# LTC.net
KiCad netlist of a schematic drawn in Altium Designer
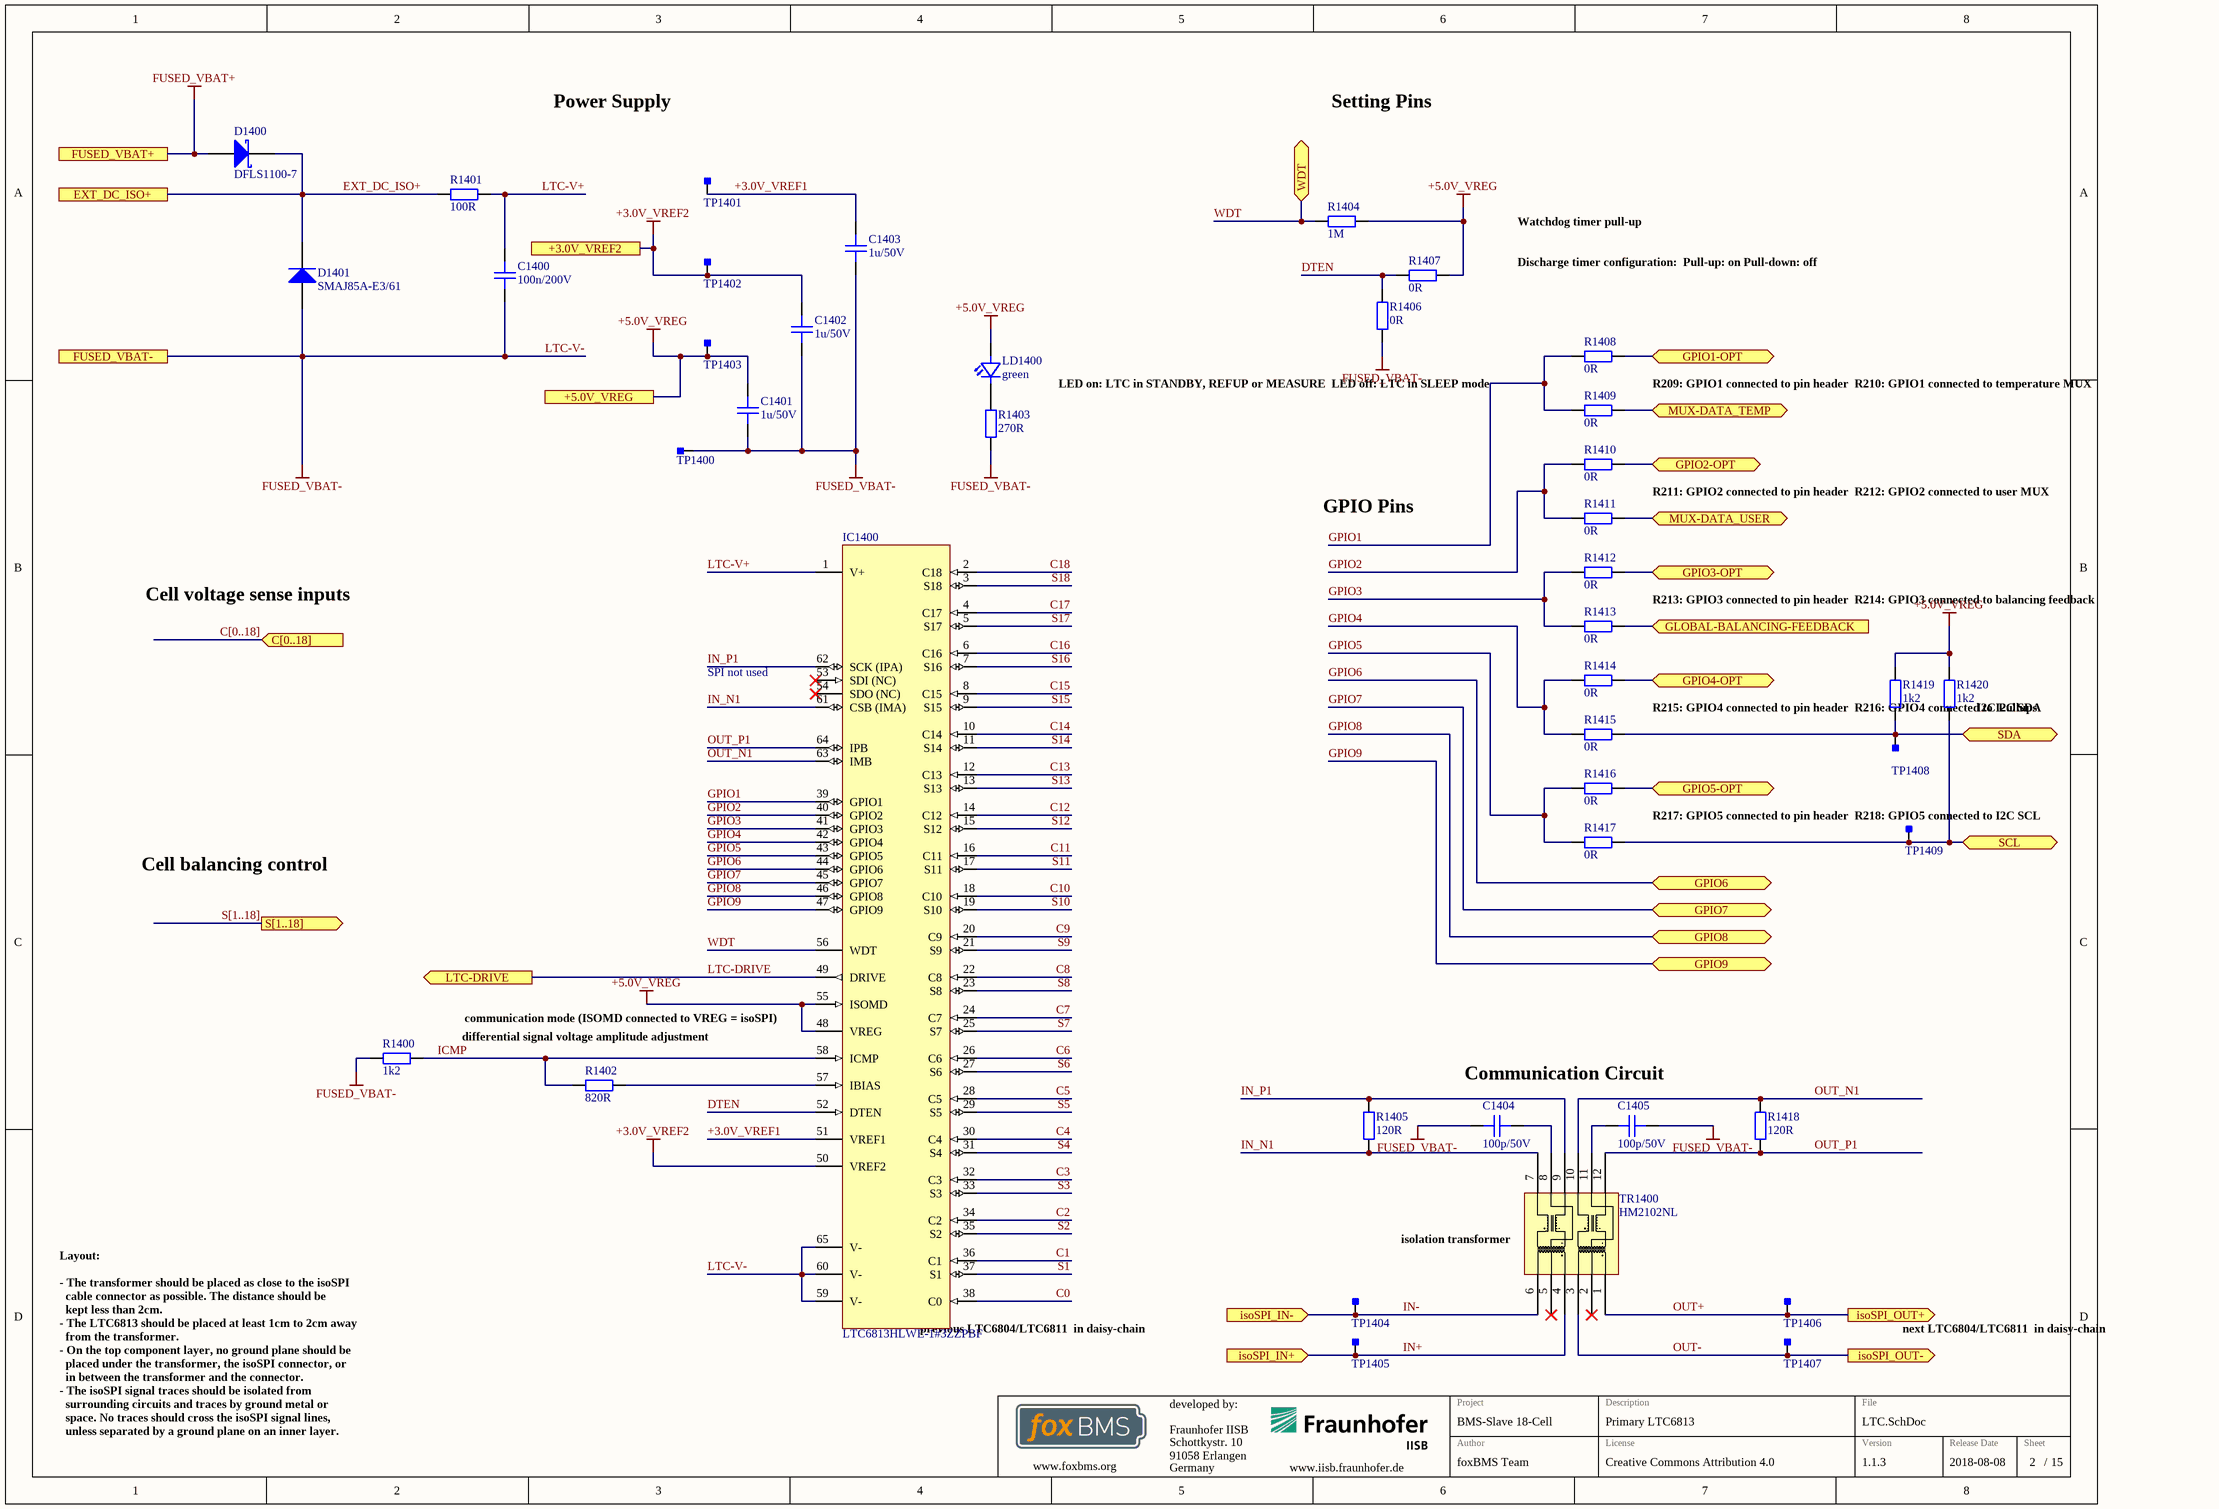
[diagram p0: LTC.SchDoc]

(export (version "E")
  (design (tool "Eeschema 10.0.6"))
  (components
    (comp (ref "C1400")
      (value "100n/200V")
      (footprint "CAPC3216X18N")
      (description "MLCC")
      (fields (field (name "PART NUMBER") "gen_C_ceramic_100n_200V_X7R_1206"))
      (libsource (lib "OE750") (part "C"))
    )
    (comp (ref "C1401")
      (value "1u/50V")
      (footprint "CAPC2012X14N")
      (description "MLCC")
      (fields (field (name "PART NUMBER") "gen_C_ceramic_1u_50V_X7R_0805") (field (name "TOLERANCE") "± 10%"))
      (libsource (lib "OE750") (part "C"))
    )
    (comp (ref "C1402")
      (value "1u/50V")
      (footprint "CAPC2012X14N")
      (description "MLCC")
      (fields (field (name "PART NUMBER") "gen_C_ceramic_1u_50V_X7R_0805") (field (name "TOLERANCE") "± 10%"))
      (libsource (lib "OE750") (part "C"))
    )
    (comp (ref "C1403")
      (value "1u/50V")
      (footprint "CAPC2012X14N")
      (description "MLCC")
      (fields (field (name "PART NUMBER") "gen_C_ceramic_1u_50V_X7R_0805") (field (name "TOLERANCE") "± 10%"))
      (libsource (lib "OE750") (part "C"))
    )
    (comp (ref "C1404")
      (value "100p/50V")
      (footprint "CAPC1608X08N")
      (description "MLCC")
      (fields
        (field (name "PART NUMBER") "gen_C_ceramic_100p_50V_C0G_0603")
        (field (name "TOLERANCE") "± 10%")
      )
      (libsource (lib "OE750") (part "C"))
    )
    (comp (ref "C1405")
      (value "100p/50V")
      (footprint "CAPC1608X08N")
      (description "MLCC")
      (fields
        (field (name "PART NUMBER") "gen_C_ceramic_100p_50V_C0G_0603")
        (field (name "TOLERANCE") "± 10%")
      )
      (libsource (lib "OE750") (part "C"))
    )
    (comp (ref "D1400")
      (value "DFLS1100-7")
      (footprint "DIOD-POWERDI123-2_V")
      (fields (field (name "MANUFACTURER") "Diodes Inc"))
      (libsource (lib "Altium Content Vault") (part "DSKY-AK-2"))
    )
    (comp (ref "D1401")
      (value "SMAJ85A-E3/61")
      (footprint "VISH-DO-214AC-2_L")
      (fields (field (name "MANUFACTURER") "Vishay Semiconductor"))
      (libsource (lib "Altium Content Vault") (part "VISH-K1A2-2"))
    )
    (comp (ref "IC1400")
      (value "LTC6813HLWE-1#3ZZPBF")
      (footprint "TSQFP50P1200X1200X160_HS-65N")
      (description "18 Cell Multicell Battery Monitor, -40 to 125 degC, Pb-Free")
      (fields (field (name "PARTNUMBER") "LTC6811HG-1#PBF") (field (name "MANUFACTURER") "Linear Technology"))
      (libsource (lib "OE750") (part "LTC6813HLWE-1#3ZZPBF"))
    )
    (comp (ref "LD1400")
      (value "green")
      (footprint "LEDC1608X07N")
      (description "TLMG1100-GS08")
      (fields (field (name "PART NUMBER") "LED_0603_green_AECQ") (field (name "MANUFACTURER") "Vishay"))
      (libsource (lib "OE750") (part "D_LED"))
    )
    (comp (ref "R1400")
      (value "1k2")
      (footprint "RESC1608X05N")
      (description "SMD Resistor 1k2 0603")
      (fields (field (name "PART NUMBER") "gen_R_1k2_0603") (field (name "TOLERANCE") "1%"))
      (libsource (lib "OE750") (part "R"))
    )
    (comp (ref "R1401")
      (value "100R")
      (footprint "RESC2012X05N")
      (description "SMD Resistor 100R 0805")
      (fields (field (name "PART NUMBER") "gen_R_100R_0805") (field (name "TOLERANCE") "1%"))
      (libsource (lib "OE750") (part "R"))
    )
    (comp (ref "R1402")
      (value "820R")
      (footprint "RESC1608X05N")
      (description "SMD Resistor 820R 0603")
      (fields (field (name "PART NUMBER") "gen_R_820R_0603") (field (name "TOLERANCE") "1%"))
      (libsource (lib "OE750") (part "R"))
    )
    (comp (ref "R1403")
      (value "270R")
      (footprint "RESC1608X05N")
      (description "SMD Resistor 270R 0603")
      (fields (field (name "PART NUMBER") "gen_R_270R_0603") (field (name "TOLERANCE") "1%"))
      (libsource (lib "OE750") (part "R"))
    )
    (comp (ref "R1404")
      (value "1M")
      (footprint "RESC1608X05N")
      (description "SMD Resistor 1M 0603")
      (fields (field (name "PART NUMBER") "gen_R_1M_0603") (field (name "TOLERANCE") "1%"))
      (libsource (lib "OE750") (part "R"))
    )
    (comp (ref "R1405")
      (value "120R")
      (footprint "RESC1608X05N")
      (description "SMD Resistor 120R 0603")
      (fields (field (name "PART NUMBER") "gen_R_120R_0603") (field (name "TOLERANCE") "1%"))
      (libsource (lib "OE750") (part "R"))
    )
    (comp (ref "R1406")
      (value "0R")
      (footprint "RESC1608X05N")
      (description "SMD Resistor 0R 0603")
      (fields (field (name "PART NUMBER") "gen_R_0R_0603") (field (name "POWER") "0.1W"))
      (libsource (lib "OE750") (part "R"))
    )
    (comp (ref "R1407")
      (value "0R")
      (footprint "RESC1608X05N")
      (description "SMD Resistor 0R 0603")
      (fields (field (name "PART NUMBER") "gen_R_0R_0603") (field (name "POWER") "0.1W"))
      (libsource (lib "OE750") (part "R"))
    )
    (comp (ref "R1408")
      (value "0R")
      (footprint "RESC1608X05N")
      (description "SMD Resistor 0R 0603")
      (fields (field (name "PART NUMBER") "gen_R_0R_0603") (field (name "POWER") "0.1W"))
      (libsource (lib "OE750") (part "R"))
    )
    (comp (ref "R1409")
      (value "0R")
      (footprint "RESC1608X05N")
      (description "SMD Resistor 0R 0603")
      (fields (field (name "PART NUMBER") "gen_R_0R_0603") (field (name "POWER") "0.1W"))
      (libsource (lib "OE750") (part "R"))
    )
    (comp (ref "R1410")
      (value "0R")
      (footprint "RESC1608X05N")
      (description "SMD Resistor 0R 0603")
      (fields (field (name "PART NUMBER") "gen_R_0R_0603") (field (name "POWER") "0.1W"))
      (libsource (lib "OE750") (part "R"))
    )
    (comp (ref "R1411")
      (value "0R")
      (footprint "RESC1608X05N")
      (description "SMD Resistor 0R 0603")
      (fields (field (name "PART NUMBER") "gen_R_0R_0603") (field (name "POWER") "0.1W"))
      (libsource (lib "OE750") (part "R"))
    )
    (comp (ref "R1412")
      (value "0R")
      (footprint "RESC1608X05N")
      (description "SMD Resistor 0R 0603")
      (fields (field (name "PART NUMBER") "gen_R_0R_0603") (field (name "POWER") "0.1W"))
      (libsource (lib "OE750") (part "R"))
    )
    (comp (ref "R1413")
      (value "0R")
      (footprint "RESC1608X05N")
      (description "SMD Resistor 0R 0603")
      (fields (field (name "PART NUMBER") "gen_R_0R_0603") (field (name "POWER") "0.1W"))
      (libsource (lib "OE750") (part "R"))
    )
    (comp (ref "R1414")
      (value "0R")
      (footprint "RESC1608X05N")
      (description "SMD Resistor 0R 0603")
      (fields (field (name "PART NUMBER") "gen_R_0R_0603") (field (name "POWER") "0.1W"))
      (libsource (lib "OE750") (part "R"))
    )
    (comp (ref "R1415")
      (value "0R")
      (footprint "RESC1608X05N")
      (description "SMD Resistor 0R 0603")
      (fields (field (name "PART NUMBER") "gen_R_0R_0603") (field (name "POWER") "0.1W"))
      (libsource (lib "OE750") (part "R"))
    )
    (comp (ref "R1416")
      (value "0R")
      (footprint "RESC1608X05N")
      (description "SMD Resistor 0R 0603")
      (fields (field (name "PART NUMBER") "gen_R_0R_0603") (field (name "POWER") "0.1W"))
      (libsource (lib "OE750") (part "R"))
    )
    (comp (ref "R1417")
      (value "0R")
      (footprint "RESC1608X05N")
      (description "SMD Resistor 0R 0603")
      (fields (field (name "PART NUMBER") "gen_R_0R_0603") (field (name "POWER") "0.1W"))
      (libsource (lib "OE750") (part "R"))
    )
    (comp (ref "R1418")
      (value "120R")
      (footprint "RESC1608X05N")
      (description "SMD Resistor 120R 0603")
      (fields (field (name "PART NUMBER") "gen_R_120R_0603") (field (name "TOLERANCE") "1%"))
      (libsource (lib "OE750") (part "R"))
    )
    (comp (ref "R1419")
      (value "1k2")
      (footprint "RESC1608X05N")
      (description "SMD Resistor 1k2 0603")
      (fields (field (name "PART NUMBER") "gen_R_1k2_0603") (field (name "TOLERANCE") "1%"))
      (libsource (lib "OE750") (part "R"))
    )
    (comp (ref "R1420")
      (value "1k2")
      (footprint "RESC1608X05N")
      (description "SMD Resistor 1k2 0603")
      (fields (field (name "PART NUMBER") "gen_R_1k2_0603") (field (name "TOLERANCE") "1%"))
      (libsource (lib "OE750") (part "R"))
    )
    (comp (ref "TP1400")
      (value "Testpoint_Square")
      (footprint "Testpoint_S1")
      (description "Testpoint, square")
      (libsource (lib "OE750") (part "Testpoint_Square"))
    )
    (comp (ref "TP1401")
      (value "Testpoint_Square")
      (footprint "Testpoint_S1")
      (description "Testpoint, square")
      (libsource (lib "OE750") (part "Testpoint_Square"))
    )
    (comp (ref "TP1402")
      (value "Testpoint_Square")
      (footprint "Testpoint_S1")
      (description "Testpoint, square")
      (libsource (lib "OE750") (part "Testpoint_Square"))
    )
    (comp (ref "TP1403")
      (value "Testpoint_Square")
      (footprint "Testpoint_S1")
      (description "Testpoint, square")
      (libsource (lib "OE750") (part "Testpoint_Square"))
    )
    (comp (ref "TP1404")
      (value "Testpoint_Square")
      (footprint "Testpoint_S1")
      (description "Testpoint, square")
      (libsource (lib "OE750") (part "Testpoint_Square"))
    )
    (comp (ref "TP1405")
      (value "Testpoint_Square")
      (footprint "Testpoint_S1")
      (description "Testpoint, square")
      (libsource (lib "OE750") (part "Testpoint_Square"))
    )
    (comp (ref "TP1406")
      (value "Testpoint_Square")
      (footprint "Testpoint_S1")
      (description "Testpoint, square")
      (libsource (lib "OE750") (part "Testpoint_Square"))
    )
    (comp (ref "TP1407")
      (value "Testpoint_Square")
      (footprint "Testpoint_S1")
      (description "Testpoint, square")
      (libsource (lib "OE750") (part "Testpoint_Square"))
    )
    (comp (ref "TP1408")
      (value "Testpoint_Square")
      (footprint "Testpoint_S1")
      (description "Testpoint, square")
      (libsource (lib "OE750") (part "Testpoint_Square"))
    )
    (comp (ref "TP1409")
      (value "Testpoint_Square")
      (footprint "Testpoint_S1")
      (description "Testpoint, square")
      (libsource (lib "OE750") (part "Testpoint_Square"))
    )
    (comp (ref "TR1400")
      (value "HM2102NL")
      (footprint "HM2102NL")
      (description "Pulse HM2102NL BMS Transformer")
      (fields (field (name "MANUFACTURER") "Pulse"))
      (libsource (lib "OE750") (part "HM2102NL"))
    )
  )
  (nets
    (net (code "1") (name "+3.0V_VREF2") (class "Default")
      (node (ref "C1402") (pin "2") (pinfunction "2_2") (pintype "passive"))
      (node (ref "IC1400") (pin "50") (pinfunction "VREF2_50") (pintype "passive"))
      (node (ref "TP1402") (pin "1") (pinfunction "1_1") (pintype "passive"))
    )
    (net (code "2") (name "+5.0V_VREG") (class "Default")
      (node (ref "C1401") (pin "2") (pinfunction "2_2") (pintype "passive"))
      (node (ref "IC1400") (pin "48") (pinfunction "VREG_48") (pintype "power_in"))
      (node (ref "IC1400") (pin "55") (pinfunction "ISOMD_55") (pintype "input"))
      (node (ref "LD1400") (pin "2") (pinfunction "A_2") (pintype "passive"))
      (node (ref "R1404") (pin "2") (pinfunction "2_2") (pintype "passive"))
      (node (ref "R1407") (pin "2") (pinfunction "2_2") (pintype "passive"))
      (node (ref "R1419") (pin "2") (pinfunction "2_2") (pintype "passive"))
      (node (ref "R1420") (pin "2") (pinfunction "2_2") (pintype "passive"))
      (node (ref "TP1403") (pin "1") (pinfunction "1_1") (pintype "passive"))
    )
    (net (code "3") (name "/+3.0V_VREF1") (class "Default")
      (node (ref "C1403") (pin "2") (pinfunction "2_2") (pintype "passive"))
      (node (ref "IC1400") (pin "51") (pinfunction "VREF1_51") (pintype "passive"))
      (node (ref "TP1401") (pin "1") (pinfunction "1_1") (pintype "passive"))
    )
    (net (code "4") (name "/C0") (class "Default")
      (node (ref "IC1400") (pin "38") (pinfunction "C0_38") (pintype "input"))
    )
    (net (code "5") (name "/C1") (class "Default")
      (node (ref "IC1400") (pin "36") (pinfunction "C1_36") (pintype "input"))
    )
    (net (code "6") (name "/C2") (class "Default")
      (node (ref "IC1400") (pin "34") (pinfunction "C2_34") (pintype "input"))
    )
    (net (code "7") (name "/C3") (class "Default")
      (node (ref "IC1400") (pin "32") (pinfunction "C3_32") (pintype "input"))
    )
    (net (code "8") (name "/C4") (class "Default")
      (node (ref "IC1400") (pin "30") (pinfunction "C4_30") (pintype "input"))
    )
    (net (code "9") (name "/C5") (class "Default")
      (node (ref "IC1400") (pin "28") (pinfunction "C5_28") (pintype "input"))
    )
    (net (code "10") (name "/C6") (class "Default")
      (node (ref "IC1400") (pin "26") (pinfunction "C6_26") (pintype "input"))
    )
    (net (code "11") (name "/C7") (class "Default")
      (node (ref "IC1400") (pin "24") (pinfunction "C7_24") (pintype "input"))
    )
    (net (code "12") (name "/C8") (class "Default")
      (node (ref "IC1400") (pin "22") (pinfunction "C8_22") (pintype "input"))
    )
    (net (code "13") (name "/C9") (class "Default")
      (node (ref "IC1400") (pin "20") (pinfunction "C9_20") (pintype "input"))
    )
    (net (code "14") (name "/C10") (class "Default")
      (node (ref "IC1400") (pin "18") (pinfunction "C10_18") (pintype "input"))
    )
    (net (code "15") (name "/C11") (class "Default")
      (node (ref "IC1400") (pin "16") (pinfunction "C11_16") (pintype "input"))
    )
    (net (code "16") (name "/C12") (class "Default")
      (node (ref "IC1400") (pin "14") (pinfunction "C12_14") (pintype "input"))
    )
    (net (code "17") (name "/C13") (class "Default")
      (node (ref "IC1400") (pin "12") (pinfunction "C13_12") (pintype "input"))
    )
    (net (code "18") (name "/C14") (class "Default")
      (node (ref "IC1400") (pin "10") (pinfunction "C14_10") (pintype "input"))
    )
    (net (code "19") (name "/C15") (class "Default")
      (node (ref "IC1400") (pin "8") (pinfunction "C15_8") (pintype "input"))
    )
    (net (code "20") (name "/C16") (class "Default")
      (node (ref "IC1400") (pin "6") (pinfunction "C16_6") (pintype "input"))
    )
    (net (code "21") (name "/C17") (class "Default")
      (node (ref "IC1400") (pin "4") (pinfunction "C17_4") (pintype "input"))
    )
    (net (code "22") (name "/C18") (class "Default")
      (node (ref "IC1400") (pin "2") (pinfunction "C18_2") (pintype "input"))
    )
    (net (code "24") (name "/DTEN") (class "Default")
      (node (ref "IC1400") (pin "52") (pinfunction "DTEN_52") (pintype "input"))
      (node (ref "R1406") (pin "2") (pinfunction "2_2") (pintype "passive"))
      (node (ref "R1407") (pin "1") (pinfunction "1_1") (pintype "passive"))
    )
    (net (code "25") (name "/EXT_DC_ISO+") (class "Default")
      (node (ref "D1400") (pin "2") (pinfunction "K_2") (pintype "passive"))
      (node (ref "D1401") (pin "1") (pinfunction "K_1") (pintype "passive"))
      (node (ref "R1401") (pin "1") (pinfunction "1_1") (pintype "passive"))
    )
    (net (code "26") (name "/GLOBAL-BALANCING-FEEDBACK") (class "Default")
      (node (ref "R1413") (pin "1") (pinfunction "1_1") (pintype "passive"))
    )
    (net (code "27") (name "/GPIO1") (class "Default")
      (node (ref "IC1400") (pin "39") (pinfunction "GPIO1_39") (pintype "bidirectional"))
      (node (ref "R1408") (pin "2") (pinfunction "2_2") (pintype "passive"))
      (node (ref "R1409") (pin "2") (pinfunction "2_2") (pintype "passive"))
    )
    (net (code "28") (name "/GPIO1-OPT") (class "Default")
      (node (ref "R1408") (pin "1") (pinfunction "1_1") (pintype "passive"))
    )
    (net (code "29") (name "/GPIO2") (class "Default")
      (node (ref "IC1400") (pin "40") (pinfunction "GPIO2_40") (pintype "bidirectional"))
      (node (ref "R1410") (pin "2") (pinfunction "2_2") (pintype "passive"))
      (node (ref "R1411") (pin "2") (pinfunction "2_2") (pintype "passive"))
    )
    (net (code "30") (name "/GPIO2-OPT") (class "Default")
      (node (ref "R1410") (pin "1") (pinfunction "1_1") (pintype "passive"))
    )
    (net (code "31") (name "/GPIO3") (class "Default")
      (node (ref "IC1400") (pin "41") (pinfunction "GPIO3_41") (pintype "bidirectional"))
      (node (ref "R1412") (pin "2") (pinfunction "2_2") (pintype "passive"))
      (node (ref "R1413") (pin "2") (pinfunction "2_2") (pintype "passive"))
    )
    (net (code "32") (name "/GPIO3-OPT") (class "Default")
      (node (ref "R1412") (pin "1") (pinfunction "1_1") (pintype "passive"))
    )
    (net (code "33") (name "/GPIO4") (class "Default")
      (node (ref "IC1400") (pin "42") (pinfunction "GPIO4_42") (pintype "bidirectional"))
      (node (ref "R1414") (pin "2") (pinfunction "2_2") (pintype "passive"))
      (node (ref "R1415") (pin "2") (pinfunction "2_2") (pintype "passive"))
    )
    (net (code "34") (name "/GPIO4-OPT") (class "Default")
      (node (ref "R1414") (pin "1") (pinfunction "1_1") (pintype "passive"))
    )
    (net (code "35") (name "/GPIO5") (class "Default")
      (node (ref "IC1400") (pin "43") (pinfunction "GPIO5_43") (pintype "bidirectional"))
      (node (ref "R1416") (pin "2") (pinfunction "2_2") (pintype "passive"))
      (node (ref "R1417") (pin "2") (pinfunction "2_2") (pintype "passive"))
    )
    (net (code "36") (name "/GPIO5-OPT") (class "Default")
      (node (ref "R1416") (pin "1") (pinfunction "1_1") (pintype "passive"))
    )
    (net (code "37") (name "/GPIO6") (class "Default")
      (node (ref "IC1400") (pin "44") (pinfunction "GPIO6_44") (pintype "bidirectional"))
    )
    (net (code "38") (name "/GPIO7") (class "Default")
      (node (ref "IC1400") (pin "45") (pinfunction "GPIO7_45") (pintype "bidirectional"))
    )
    (net (code "39") (name "/GPIO8") (class "Default")
      (node (ref "IC1400") (pin "46") (pinfunction "GPIO8_46") (pintype "bidirectional"))
    )
    (net (code "40") (name "/GPIO9") (class "Default")
      (node (ref "IC1400") (pin "47") (pinfunction "GPIO9_47") (pintype "bidirectional"))
    )
    (net (code "41") (name "/ICMP") (class "Default")
      (node (ref "IC1400") (pin "58") (pinfunction "ICMP_58") (pintype "input"))
      (node (ref "R1400") (pin "2") (pinfunction "2_2") (pintype "passive"))
      (node (ref "R1402") (pin "1") (pinfunction "1_1") (pintype "passive"))
    )
    (net (code "42") (name "/IN+") (class "Default")
      (node (ref "TP1405") (pin "1") (pinfunction "1_1") (pintype "passive"))
      (node (ref "TR1400") (pin "4") (pintype "passive"))
    )
    (net (code "43") (name "/IN-") (class "Default")
      (node (ref "TP1404") (pin "1") (pinfunction "1_1") (pintype "passive"))
      (node (ref "TR1400") (pin "6") (pintype "passive"))
    )
    (net (code "44") (name "/IN_N1") (class "Default")
      (node (ref "IC1400") (pin "61") (pinfunction "CSB_(IMA)_61") (pintype "bidirectional"))
      (node (ref "R1405") (pin "2") (pinfunction "2_2") (pintype "passive"))
      (node (ref "TR1400") (pin "7") (pintype "passive"))
    )
    (net (code "45") (name "/IN_P1") (class "Default")
      (node (ref "IC1400") (pin "62") (pinfunction "SCK_(IPA)_62") (pintype "bidirectional"))
      (node (ref "R1405") (pin "1") (pinfunction "1_1") (pintype "passive"))
      (node (ref "TR1400") (pin "9") (pintype "passive"))
    )
    (net (code "46") (name "/LTC-DRIVE") (class "Default")
      (node (ref "IC1400") (pin "49") (pinfunction "DRIVE_49") (pintype "output"))
    )
    (net (code "47") (name "/LTC-V+") (class "Default")
      (node (ref "C1400") (pin "1") (pinfunction "1_1") (pintype "passive"))
      (node (ref "IC1400") (pin "1") (pinfunction "V+_1") (pintype "power_in"))
      (node (ref "R1401") (pin "2") (pinfunction "2_2") (pintype "passive"))
    )
    (net (code "48") (name "/MUX-DATA_TEMP") (class "Default")
      (node (ref "R1409") (pin "1") (pinfunction "1_1") (pintype "passive"))
    )
    (net (code "49") (name "/MUX-DATA_USER") (class "Default")
      (node (ref "R1411") (pin "1") (pinfunction "1_1") (pintype "passive"))
    )
    (net (code "50") (name "/OUT+") (class "Default")
      (node (ref "TP1406") (pin "1") (pinfunction "1_1") (pintype "passive"))
      (node (ref "TR1400") (pin "1") (pintype "passive"))
    )
    (net (code "51") (name "/OUT-") (class "Default")
      (node (ref "TP1407") (pin "1") (pinfunction "1_1") (pintype "passive"))
      (node (ref "TR1400") (pin "3") (pintype "passive"))
    )
    (net (code "52") (name "/OUT_N1") (class "Default")
      (node (ref "IC1400") (pin "63") (pinfunction "IMB_63") (pintype "bidirectional"))
      (node (ref "R1418") (pin "2") (pinfunction "2_2") (pintype "passive"))
      (node (ref "TR1400") (pin "10") (pintype "passive"))
    )
    (net (code "53") (name "/OUT_P1") (class "Default")
      (node (ref "IC1400") (pin "64") (pinfunction "IPB_64") (pintype "bidirectional"))
      (node (ref "R1418") (pin "1") (pinfunction "1_1") (pintype "passive"))
      (node (ref "TR1400") (pin "12") (pintype "passive"))
    )
    (net (code "54") (name "/S1") (class "Default")
      (node (ref "IC1400") (pin "37") (pinfunction "S1_37") (pintype "bidirectional"))
    )
    (net (code "55") (name "/S2") (class "Default")
      (node (ref "IC1400") (pin "35") (pinfunction "S2_35") (pintype "bidirectional"))
    )
    (net (code "56") (name "/S3") (class "Default")
      (node (ref "IC1400") (pin "33") (pinfunction "S3_33") (pintype "bidirectional"))
    )
    (net (code "57") (name "/S4") (class "Default")
      (node (ref "IC1400") (pin "31") (pinfunction "S4_31") (pintype "bidirectional"))
    )
    (net (code "58") (name "/S5") (class "Default")
      (node (ref "IC1400") (pin "29") (pinfunction "S5_29") (pintype "bidirectional"))
    )
    (net (code "59") (name "/S6") (class "Default")
      (node (ref "IC1400") (pin "27") (pinfunction "S6_27") (pintype "bidirectional"))
    )
    (net (code "60") (name "/S7") (class "Default")
      (node (ref "IC1400") (pin "25") (pinfunction "S7_25") (pintype "bidirectional"))
    )
    (net (code "61") (name "/S8") (class "Default")
      (node (ref "IC1400") (pin "23") (pinfunction "S8_23") (pintype "bidirectional"))
    )
    (net (code "62") (name "/S9") (class "Default")
      (node (ref "IC1400") (pin "21") (pinfunction "S9_21") (pintype "bidirectional"))
    )
    (net (code "63") (name "/S10") (class "Default")
      (node (ref "IC1400") (pin "19") (pinfunction "S10_19") (pintype "bidirectional"))
    )
    (net (code "64") (name "/S11") (class "Default")
      (node (ref "IC1400") (pin "17") (pinfunction "S11_17") (pintype "bidirectional"))
    )
    (net (code "65") (name "/S12") (class "Default")
      (node (ref "IC1400") (pin "15") (pinfunction "S12_15") (pintype "bidirectional"))
    )
    (net (code "66") (name "/S13") (class "Default")
      (node (ref "IC1400") (pin "13") (pinfunction "S13_13") (pintype "bidirectional"))
    )
    (net (code "67") (name "/S14") (class "Default")
      (node (ref "IC1400") (pin "11") (pinfunction "S14_11") (pintype "bidirectional"))
    )
    (net (code "68") (name "/S15") (class "Default")
      (node (ref "IC1400") (pin "9") (pinfunction "S15_9") (pintype "bidirectional"))
    )
    (net (code "69") (name "/S16") (class "Default")
      (node (ref "IC1400") (pin "7") (pinfunction "S16_7") (pintype "bidirectional"))
    )
    (net (code "70") (name "/S17") (class "Default")
      (node (ref "IC1400") (pin "5") (pinfunction "S17_5") (pintype "bidirectional"))
    )
    (net (code "71") (name "/S18") (class "Default")
      (node (ref "IC1400") (pin "3") (pinfunction "S18_3") (pintype "bidirectional"))
    )
    (net (code "72") (name "/SCL") (class "Default")
      (node (ref "R1417") (pin "1") (pinfunction "1_1") (pintype "passive"))
      (node (ref "R1420") (pin "1") (pinfunction "1_1") (pintype "passive"))
      (node (ref "TP1409") (pin "1") (pinfunction "1_1") (pintype "passive"))
    )
    (net (code "73") (name "/SDA") (class "Default")
      (node (ref "R1415") (pin "1") (pinfunction "1_1") (pintype "passive"))
      (node (ref "R1419") (pin "1") (pinfunction "1_1") (pintype "passive"))
      (node (ref "TP1408") (pin "1") (pinfunction "1_1") (pintype "passive"))
    )
    (net (code "75") (name "/WDT") (class "Default")
      (node (ref "IC1400") (pin "56") (pinfunction "WDT_56") (pintype "tri_state"))
      (node (ref "R1404") (pin "1") (pinfunction "1_1") (pintype "passive"))
    )
    (net (code "76") (name "FUSED_VBAT+") (class "Default")
      (node (ref "D1400") (pin "1") (pinfunction "A_1") (pintype "passive"))
    )
    (net (code "77") (name "FUSED_VBAT-") (class "Default")
      (node (ref "C1400") (pin "2") (pinfunction "2_2") (pintype "passive"))
      (node (ref "C1401") (pin "1") (pinfunction "1_1") (pintype "passive"))
      (node (ref "C1402") (pin "1") (pinfunction "1_1") (pintype "passive"))
      (node (ref "C1403") (pin "1") (pinfunction "1_1") (pintype "passive"))
      (node (ref "C1404") (pin "1") (pinfunction "1_1") (pintype "passive"))
      (node (ref "C1405") (pin "1") (pinfunction "1_1") (pintype "passive"))
      (node (ref "D1401") (pin "2") (pinfunction "A_2") (pintype "passive"))
      (node (ref "IC1400") (pin "59") (pinfunction "V-_59") (pintype "power_in"))
      (node (ref "IC1400") (pin "60") (pinfunction "V-_60") (pintype "power_in"))
      (node (ref "IC1400") (pin "65") (pinfunction "V-_65") (pintype "power_in"))
      (node (ref "R1400") (pin "1") (pinfunction "1_1") (pintype "passive"))
      (node (ref "R1403") (pin "1") (pinfunction "1_1") (pintype "passive"))
      (node (ref "R1406") (pin "1") (pinfunction "1_1") (pintype "passive"))
      (node (ref "TP1400") (pin "1") (pinfunction "1_1") (pintype "passive"))
    )
    (net (code "78") (name "Net-(C1404-Pad2)") (class "Default")
      (node (ref "C1404") (pin "2") (pinfunction "2_2") (pintype "passive"))
      (node (ref "TR1400") (pin "8") (pintype "passive"))
    )
    (net (code "79") (name "Net-(C1405-Pad2)") (class "Default")
      (node (ref "C1405") (pin "2") (pinfunction "2_2") (pintype "passive"))
      (node (ref "TR1400") (pin "11") (pintype "passive"))
    )
    (net (code "80") (name "Net-(IC1400-IBIAS)") (class "Default")
      (node (ref "IC1400") (pin "57") (pinfunction "IBIAS_57") (pintype "input"))
      (node (ref "R1402") (pin "2") (pinfunction "2_2") (pintype "passive"))
    )
    (net (code "81") (name "Net-(LD1400-C)") (class "Default")
      (node (ref "LD1400") (pin "1") (pinfunction "C_1") (pintype "passive"))
      (node (ref "R1403") (pin "2") (pinfunction "2_2") (pintype "passive"))
    )
    (net (code "82") (name "unconnected-(IC1400-SDI_(NC)-Pad53)") (class "Default")
      (node (ref "IC1400") (pin "53") (pinfunction "SDI_(NC)_53") (pintype "input+no_connect"))
    )
    (net (code "83") (name "unconnected-(IC1400-SDO_(NC)-Pad54)") (class "Default")
      (node (ref "IC1400") (pin "54") (pinfunction "SDO_(NC)_54") (pintype "open_collector+no_connect"))
    )
    (net (code "84") (name "unconnected-(TR1400-Pad2)") (class "Default")
      (node (ref "TR1400") (pin "2") (pintype "passive+no_connect"))
    )
    (net (code "85") (name "unconnected-(TR1400-Pad5)") (class "Default")
      (node (ref "TR1400") (pin "5") (pintype "passive+no_connect"))
    )
  )
)
